# ATTAMI-Shield-sounday.net
KiCad netlist of a schematic drawn in EAGLE
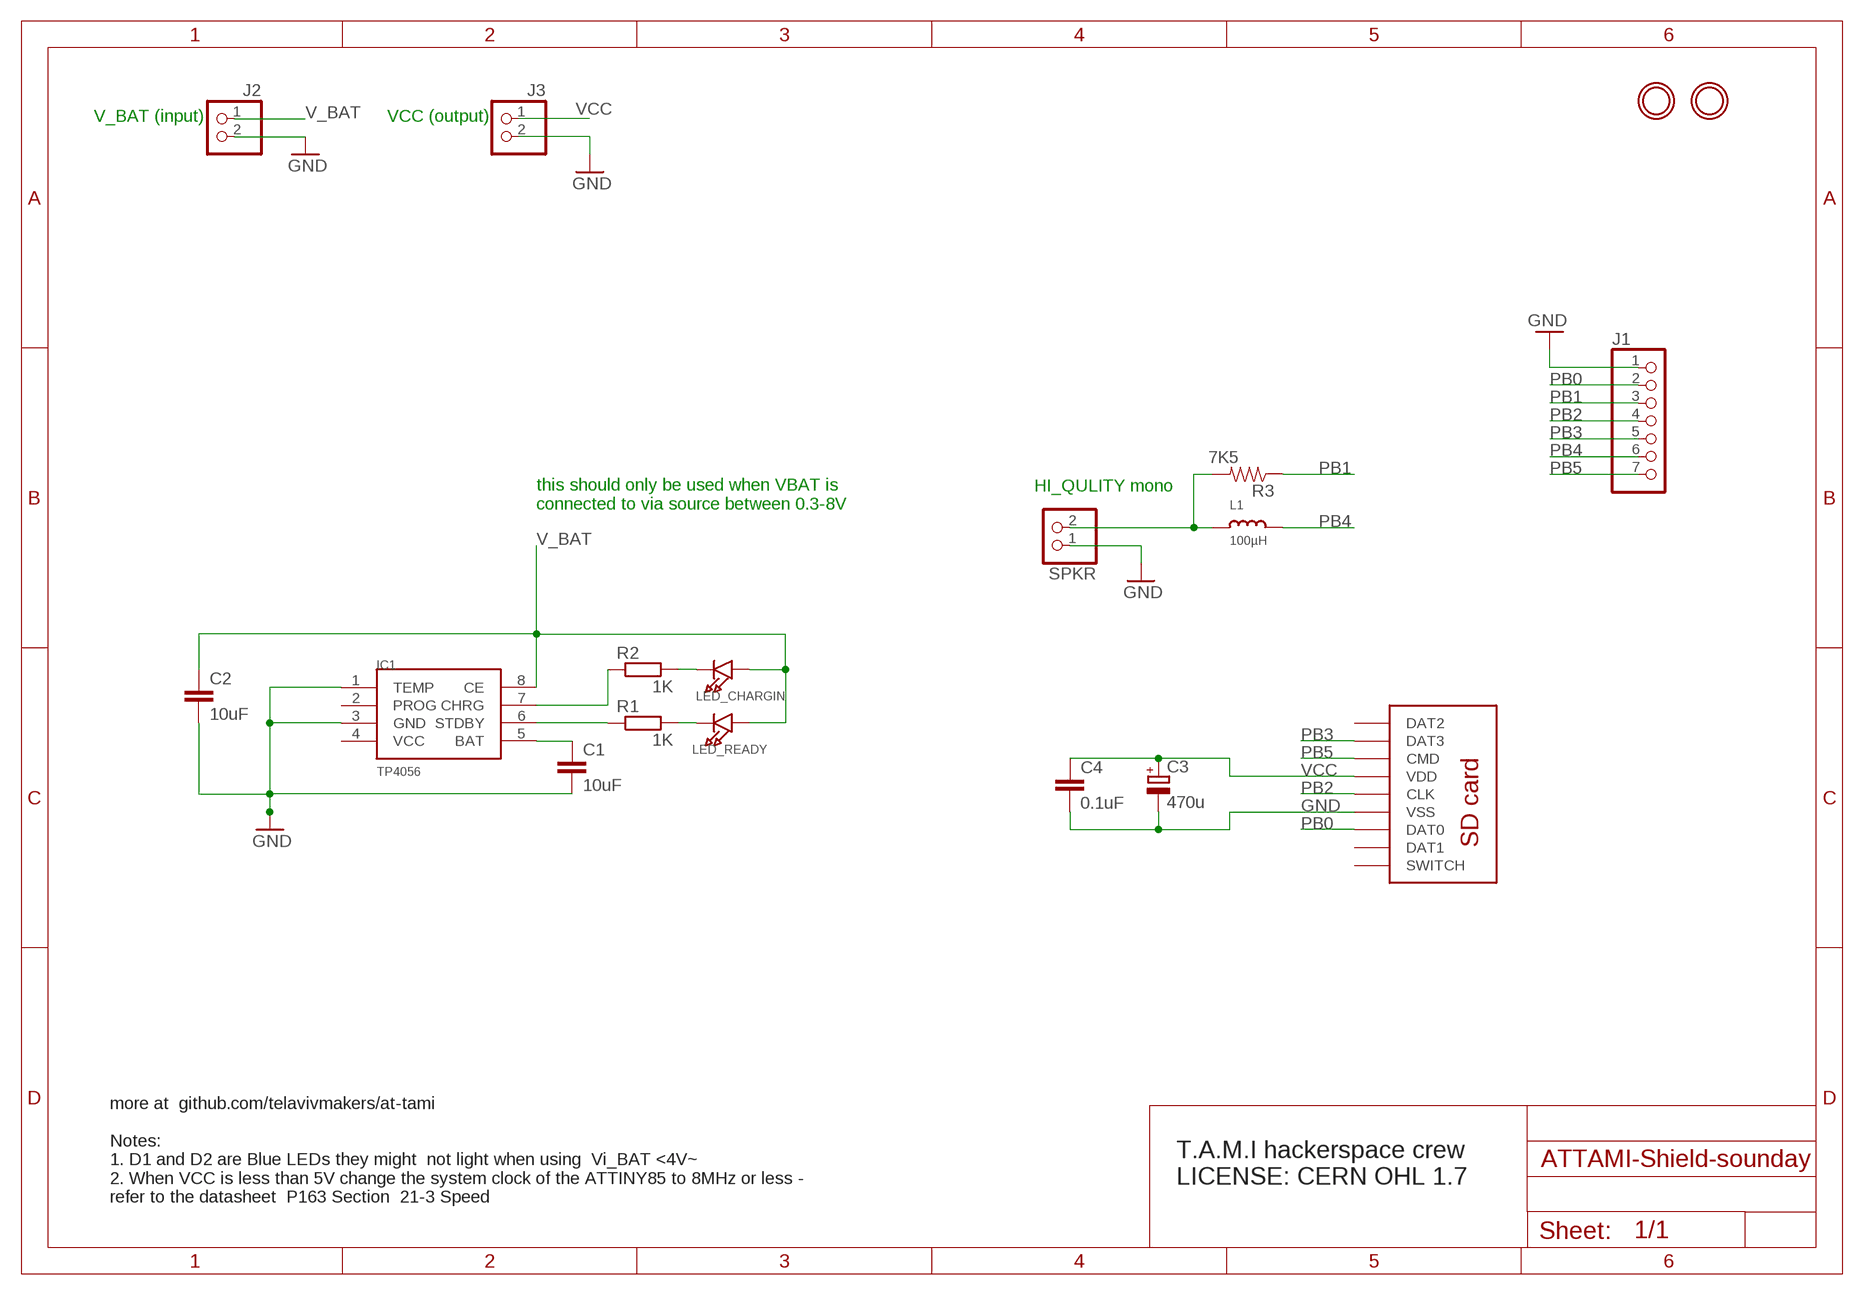
[diagram p0: schematic, sheet 1]

(export (version "E")
  (design (tool "Eeschema 10.0.6"))
  (components
    (comp (ref "C1")
      (value "10uF")
      (footprint "eagle-import:1206")
      (libsource (lib "eagle-import") (part "10UF-6.3V-20%(1206)"))
    )
    (comp (ref "C2")
      (value "10uF")
      (footprint "eagle-import:1206")
      (libsource (lib "eagle-import") (part "10UF-6.3V-20%(1206)"))
    )
    (comp (ref "C3")
      (value "470u")
      (footprint "eagle-import:CASE_A")
      (libsource (lib "eagle-import") (part "CAPACITOR_POL-CASE_A"))
    )
    (comp (ref "C4")
      (value "0.1uF")
      (footprint "eagle-import:0603-CAP")
      (libsource (lib "eagle-import") (part "0.1UF-25V(+80/-20%)(0603)"))
    )
    (comp (ref "IC1")
      (value "TP4056")
      (footprint "eagle-import:SOP-8")
      (libsource (lib "eagle-import") (part "TP4056"))
    )
    (comp (ref "J1")
      (value "HEADER-1X7ROUND")
      (footprint "eagle-import:1X07_ROUND")
      (libsource (lib "eagle-import") (part "HEADER-1X7ROUND"))
    )
    (comp (ref "J2")
      (value "HEADER-1X2ROUND")
      (footprint "eagle-import:1X02_ROUND")
      (libsource (lib "eagle-import") (part "HEADER-1X2ROUND"))
    )
    (comp (ref "J3")
      (value "HEADER-1X2ROUND")
      (footprint "eagle-import:1X02_ROUND")
      (libsource (lib "eagle-import") (part "HEADER-1X2ROUND"))
    )
    (comp (ref "L1")
      (value "100µH")
      (footprint "eagle-import:0805")
      (libsource (lib "eagle-import") (part "INDUCTOR0805"))
    )
    (comp (ref "LED_CHARGIN")
      (value "LED0805_NOOUTLINE")
      (footprint "eagle-import:CHIPLED_0805_NOOUTLINE")
      (libsource (lib "eagle-import") (part "LED0805_NOOUTLINE"))
    )
    (comp (ref "LED_READY")
      (value "LED0805_NOOUTLINE")
      (footprint "eagle-import:CHIPLED_0805_NOOUTLINE")
      (libsource (lib "eagle-import") (part "LED0805_NOOUTLINE"))
    )
    (comp (ref "R1")
      (value "1K")
      (footprint "eagle-import:R603")
      (libsource (lib "eagle-import") (part "RESISTOR-0603"))
    )
    (comp (ref "R2")
      (value "1K")
      (footprint "eagle-import:R603")
      (libsource (lib "eagle-import") (part "RESISTOR-0603"))
    )
    (comp (ref "R3")
      (value "7K5")
      (footprint "eagle-import:0805")
      (libsource (lib "eagle-import") (part "RESISTOR0805-RES"))
    )
    (comp (ref "SPKR")
      (value "HEADER-1X2ROUND")
      (footprint "eagle-import:1X02_ROUND")
      (libsource (lib "eagle-import") (part "HEADER-1X2ROUND"))
    )
    (comp (ref "U$1")
      (value "MOUNTINGHOLE2.0")
      (footprint "eagle-import:MOUNTINGHOLE_2.0_PLATED")
      (libsource (lib "eagle-import") (part "MOUNTINGHOLE2.0"))
    )
    (comp (ref "U$2")
      (value "MOUNTINGHOLE2.0")
      (footprint "eagle-import:MOUNTINGHOLE_2.0_PLATED")
      (libsource (lib "eagle-import") (part "MOUNTINGHOLE2.0"))
    )
    (comp (ref "U$4")
      (value "MOLEX-SD-105027")
      (footprint "eagle-import:MOLEX-SD-105027-PKG")
      (libsource (lib "eagle-import") (part "MOLEX-SD-105027"))
    )
  )
  (nets
    (net (code "1") (name "/PB0") (class "Default")
      (node (ref "J1") (pin "2") (pinfunction "2_2") (pintype "passive"))
      (node (ref "U$4") (pin "P$7") (pinfunction "DAT0_P$7") (pintype "bidirectional"))
    )
    (net (code "2") (name "/PB1") (class "Default")
      (node (ref "J1") (pin "3") (pinfunction "3_3") (pintype "passive"))
      (node (ref "R3") (pin "1") (pinfunction "1_1") (pintype "passive"))
    )
    (net (code "3") (name "/PB2") (class "Default")
      (node (ref "J1") (pin "4") (pinfunction "4_4") (pintype "passive"))
      (node (ref "U$4") (pin "P$5") (pinfunction "CLK_P$5") (pintype "bidirectional"))
    )
    (net (code "4") (name "/PB3") (class "Default")
      (node (ref "J1") (pin "5") (pinfunction "5_5") (pintype "passive"))
      (node (ref "U$4") (pin "P$2") (pinfunction "DAT3_P$2") (pintype "bidirectional"))
    )
    (net (code "5") (name "/PB4") (class "Default")
      (node (ref "J1") (pin "6") (pinfunction "6_6") (pintype "passive"))
      (node (ref "L1") (pin "2") (pinfunction "2_2") (pintype "passive"))
    )
    (net (code "6") (name "/PB5") (class "Default")
      (node (ref "J1") (pin "7") (pinfunction "7_7") (pintype "passive"))
      (node (ref "U$4") (pin "P$3") (pinfunction "CMD_P$3") (pintype "bidirectional"))
    )
    (net (code "7") (name "/VCC") (class "Default")
      (node (ref "C3") (pin "+") (pinfunction "+_+") (pintype "passive"))
      (node (ref "C4") (pin "1") (pinfunction "1_1") (pintype "passive"))
      (node (ref "J3") (pin "1") (pinfunction "1_1") (pintype "passive"))
      (node (ref "U$4") (pin "P$4") (pinfunction "VDD_P$4") (pintype "bidirectional"))
    )
    (net (code "8") (name "/V_BAT") (class "Default")
      (node (ref "C2") (pin "1") (pinfunction "1_1") (pintype "passive"))
      (node (ref "IC1") (pin "8") (pinfunction "CE_8") (pintype "bidirectional"))
      (node (ref "J2") (pin "1") (pinfunction "1_1") (pintype "passive"))
      (node (ref "LED_CHARGIN") (pin "A") (pinfunction "A_A") (pintype "passive"))
      (node (ref "LED_READY") (pin "A") (pinfunction "A_A") (pintype "passive"))
    )
    (net (code "9") (name "GND") (class "Default")
      (node (ref "C1") (pin "2") (pinfunction "2_2") (pintype "passive"))
      (node (ref "C2") (pin "2") (pinfunction "2_2") (pintype "passive"))
      (node (ref "C3") (pin "-") (pinfunction "-_-") (pintype "passive"))
      (node (ref "C4") (pin "2") (pinfunction "2_2") (pintype "passive"))
      (node (ref "IC1") (pin "1") (pinfunction "TEMP_1") (pintype "bidirectional"))
      (node (ref "IC1") (pin "3") (pinfunction "GND_3") (pintype "bidirectional"))
      (node (ref "J1") (pin "1") (pinfunction "1_1") (pintype "passive"))
      (node (ref "J2") (pin "2") (pinfunction "2_2") (pintype "passive"))
      (node (ref "J3") (pin "2") (pinfunction "2_2") (pintype "passive"))
      (node (ref "SPKR") (pin "1") (pinfunction "1_1") (pintype "passive"))
      (node (ref "U$4") (pin "P$6") (pinfunction "VSS_P$6") (pintype "bidirectional"))
    )
    (net (code "10") (name "Net-(IC1-BAT)") (class "Default")
      (node (ref "C1") (pin "1") (pinfunction "1_1") (pintype "passive"))
      (node (ref "IC1") (pin "5") (pinfunction "BAT_5") (pintype "bidirectional"))
    )
    (net (code "11") (name "Net-(IC1-CHRG)") (class "Default")
      (node (ref "IC1") (pin "7") (pinfunction "CHRG_7") (pintype "bidirectional"))
      (node (ref "R2") (pin "1") (pinfunction "1_1") (pintype "passive"))
    )
    (net (code "12") (name "Net-(IC1-STDBY)") (class "Default")
      (node (ref "IC1") (pin "6") (pinfunction "STDBY_6") (pintype "bidirectional"))
      (node (ref "R1") (pin "1") (pinfunction "1_1") (pintype "passive"))
    )
    (net (code "13") (name "Net-(L1-Pad1)") (class "Default")
      (node (ref "L1") (pin "1") (pinfunction "1_1") (pintype "passive"))
      (node (ref "R3") (pin "2") (pinfunction "2_2") (pintype "passive"))
      (node (ref "SPKR") (pin "2") (pinfunction "2_2") (pintype "passive"))
    )
    (net (code "14") (name "Net-(LED_CHARGIN-PadC)") (class "Default")
      (node (ref "LED_CHARGIN") (pin "C") (pinfunction "C_C") (pintype "passive"))
      (node (ref "R2") (pin "2") (pinfunction "2_2") (pintype "passive"))
    )
    (net (code "15") (name "Net-(LED_READY-PadC)") (class "Default")
      (node (ref "LED_READY") (pin "C") (pinfunction "C_C") (pintype "passive"))
      (node (ref "R1") (pin "2") (pinfunction "2_2") (pintype "passive"))
    )
    (net (code "16") (name "unconnected-(IC1-PROG-Pad2)") (class "Default")
      (node (ref "IC1") (pin "2") (pinfunction "PROG_2") (pintype "bidirectional"))
    )
    (net (code "17") (name "unconnected-(IC1-VCC-Pad4)") (class "Default")
      (node (ref "IC1") (pin "4") (pinfunction "VCC_4") (pintype "bidirectional"))
    )
    (net (code "18") (name "unconnected-(U$4-DAT1-PadP$8)") (class "Default")
      (node (ref "U$4") (pin "P$8") (pinfunction "DAT1_P$8") (pintype "bidirectional"))
    )
    (net (code "19") (name "unconnected-(U$4-DAT2-PadP$1)") (class "Default")
      (node (ref "U$4") (pin "P$1") (pinfunction "DAT2_P$1") (pintype "bidirectional"))
    )
    (net (code "20") (name "unconnected-(U$4-SWITCH-PadG$1)") (class "Default")
      (node (ref "U$4") (pin "G$1") (pinfunction "SWITCH_G$1") (pintype "bidirectional"))
    )
  )
)
